# Paralel_NOR_FLASH.net
KiCad netlist of a schematic drawn in Altium Designer
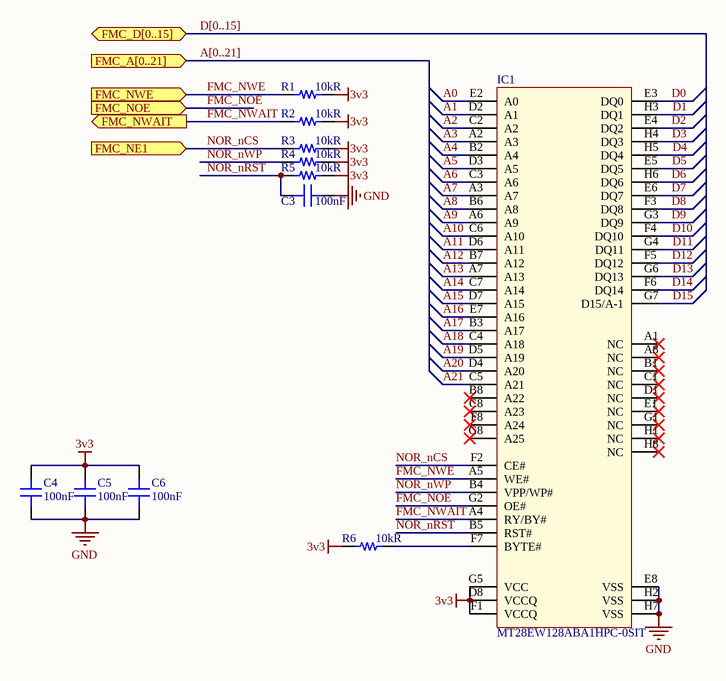
[diagram p0: Paralel NOR FLASH.SchDoc]

(export (version "E")
  (design (tool "Eeschema 10.0.6"))
  (components
    (comp (ref "C3")
      (value "100nF")
      (footprint "CAP 0603/1608")
      (description "Ceramic, SMT Capacitor")
      (fields
        (field (name "MANUFACTURER") "Samsung")
        (field (name "MANUFACTURER PART NUMBER") "CL10B104JB8NNNC")
      )
      (libsource (lib "yildizIoT Library") (part "Capacitor - Ceramic"))
    )
    (comp (ref "C4")
      (value "100nF")
      (footprint "CAP 0603/1608")
      (description "Ceramic, SMT Capacitor")
      (fields
        (field (name "MANUFACTURER") "Samsung")
        (field (name "MANUFACTURER PART NUMBER") "CL10B104JB8NNNC")
      )
      (libsource (lib "yildizIoT Library") (part "Capacitor - Ceramic"))
    )
    (comp (ref "C5")
      (value "100nF")
      (footprint "CAP 0603/1608")
      (description "Ceramic, SMT Capacitor")
      (fields
        (field (name "MANUFACTURER") "Samsung")
        (field (name "MANUFACTURER PART NUMBER") "CL10B104JB8NNNC")
      )
      (libsource (lib "yildizIoT Library") (part "Capacitor - Ceramic"))
    )
    (comp (ref "C6")
      (value "100nF")
      (footprint "CAP 0603/1608")
      (description "Ceramic, SMT Capacitor")
      (fields
        (field (name "MANUFACTURER") "Samsung")
        (field (name "MANUFACTURER PART NUMBER") "CL10B104JB8NNNC")
      )
      (libsource (lib "yildizIoT Library") (part "Capacitor - Ceramic"))
    )
    (comp (ref "IC1")
      (value "MT28EW128ABA1HPC-0SIT")
      (footprint "MICRON LBGA-64 11X13mm")
      (description "Parallel NOR Flash Embedded Memory")
      (fields (field (name "MANUFACTURER") "Micron Technology"))
      (libsource (lib "yildizIoT Library") (part "MICRON MT28EW128"))
    )
    (comp (ref "R1")
      (value "10kR")
      (footprint "RES 0603/1608")
      (description "Ceramic, SMT Capacitor")
      (fields
        (field (name "MANUFACTURER") "Stackpole Electronics")
        (field (name "MANUFACTURER PART NUMBER") "RNCP0603FTD10K0")
      )
      (libsource (lib "yildizIoT Library") (part "Resistor_Chip"))
    )
    (comp (ref "R2")
      (value "10kR")
      (footprint "RES 0603/1608")
      (description "Ceramic, SMT Capacitor")
      (fields
        (field (name "MANUFACTURER") "Stackpole Electronics")
        (field (name "MANUFACTURER PART NUMBER") "RNCP0603FTD10K0")
      )
      (libsource (lib "yildizIoT Library") (part "Resistor_Chip"))
    )
    (comp (ref "R3")
      (value "10kR")
      (footprint "RES 0603/1608")
      (description "Ceramic, SMT Capacitor")
      (fields
        (field (name "MANUFACTURER") "Stackpole Electronics")
        (field (name "MANUFACTURER PART NUMBER") "RNCP0603FTD10K0")
      )
      (libsource (lib "yildizIoT Library") (part "Resistor_Chip"))
    )
    (comp (ref "R4")
      (value "10kR")
      (footprint "RES 0603/1608")
      (description "Ceramic, SMT Capacitor")
      (fields
        (field (name "MANUFACTURER") "Stackpole Electronics")
        (field (name "MANUFACTURER PART NUMBER") "RNCP0603FTD10K0")
      )
      (libsource (lib "yildizIoT Library") (part "Resistor_Chip"))
    )
    (comp (ref "R5")
      (value "10kR")
      (footprint "RES 0603/1608")
      (description "Ceramic, SMT Capacitor")
      (fields
        (field (name "MANUFACTURER") "Stackpole Electronics")
        (field (name "MANUFACTURER PART NUMBER") "RNCP0603FTD10K0")
      )
      (libsource (lib "yildizIoT Library") (part "Resistor_Chip"))
    )
    (comp (ref "R6")
      (value "10kR")
      (footprint "RES 0603/1608")
      (description "Ceramic, SMT Capacitor")
      (fields
        (field (name "MANUFACTURER") "Stackpole Electronics")
        (field (name "MANUFACTURER PART NUMBER") "RNCP0603FTD10K0")
      )
      (libsource (lib "yildizIoT Library") (part "Resistor_Chip"))
    )
  )
  (nets
    (net (code "1") (name "/A0") (class "Default")
      (node (ref "IC1") (pin "E2") (pinfunction "A0_E2") (pintype "passive"))
    )
    (net (code "2") (name "/A1") (class "Default")
      (node (ref "IC1") (pin "D2") (pinfunction "A1_D2") (pintype "passive"))
    )
    (net (code "3") (name "/A2") (class "Default")
      (node (ref "IC1") (pin "C2") (pinfunction "A2_C2") (pintype "passive"))
    )
    (net (code "4") (name "/A3") (class "Default")
      (node (ref "IC1") (pin "A2") (pinfunction "A3_A2") (pintype "passive"))
    )
    (net (code "5") (name "/A4") (class "Default")
      (node (ref "IC1") (pin "B2") (pinfunction "A4_B2") (pintype "passive"))
    )
    (net (code "6") (name "/A5") (class "Default")
      (node (ref "IC1") (pin "D3") (pinfunction "A5_D3") (pintype "passive"))
    )
    (net (code "7") (name "/A6") (class "Default")
      (node (ref "IC1") (pin "C3") (pinfunction "A6_C3") (pintype "passive"))
    )
    (net (code "8") (name "/A7") (class "Default")
      (node (ref "IC1") (pin "A3") (pinfunction "A7_A3") (pintype "passive"))
    )
    (net (code "9") (name "/A8") (class "Default")
      (node (ref "IC1") (pin "B6") (pinfunction "A8_B6") (pintype "passive"))
    )
    (net (code "10") (name "/A9") (class "Default")
      (node (ref "IC1") (pin "A6") (pinfunction "A9_A6") (pintype "passive"))
    )
    (net (code "11") (name "/A10") (class "Default")
      (node (ref "IC1") (pin "C6") (pinfunction "A10_C6") (pintype "passive"))
    )
    (net (code "12") (name "/A11") (class "Default")
      (node (ref "IC1") (pin "D6") (pinfunction "A11_D6") (pintype "passive"))
    )
    (net (code "13") (name "/A12") (class "Default")
      (node (ref "IC1") (pin "B7") (pinfunction "A12_B7") (pintype "passive"))
    )
    (net (code "14") (name "/A13") (class "Default")
      (node (ref "IC1") (pin "A7") (pinfunction "A13_A7") (pintype "passive"))
    )
    (net (code "15") (name "/A14") (class "Default")
      (node (ref "IC1") (pin "C7") (pinfunction "A14_C7") (pintype "passive"))
    )
    (net (code "16") (name "/A15") (class "Default")
      (node (ref "IC1") (pin "D7") (pinfunction "A15_D7") (pintype "passive"))
    )
    (net (code "17") (name "/A16") (class "Default")
      (node (ref "IC1") (pin "E7") (pinfunction "A16_E7") (pintype "passive"))
    )
    (net (code "18") (name "/A17") (class "Default")
      (node (ref "IC1") (pin "B3") (pinfunction "A17_B3") (pintype "passive"))
    )
    (net (code "19") (name "/A18") (class "Default")
      (node (ref "IC1") (pin "C4") (pinfunction "A18_C4") (pintype "passive"))
    )
    (net (code "20") (name "/A19") (class "Default")
      (node (ref "IC1") (pin "D5") (pinfunction "A19_D5") (pintype "passive"))
    )
    (net (code "21") (name "/A20") (class "Default")
      (node (ref "IC1") (pin "D4") (pinfunction "A20_D4") (pintype "passive"))
    )
    (net (code "22") (name "/A21") (class "Default")
      (node (ref "IC1") (pin "C5") (pinfunction "A21_C5") (pintype "passive"))
    )
    (net (code "24") (name "/D0") (class "Default")
      (node (ref "IC1") (pin "E3") (pinfunction "DQ0_E3") (pintype "passive"))
    )
    (net (code "25") (name "/D1") (class "Default")
      (node (ref "IC1") (pin "H3") (pinfunction "DQ1_H3") (pintype "passive"))
    )
    (net (code "26") (name "/D2") (class "Default")
      (node (ref "IC1") (pin "E4") (pinfunction "DQ2_E4") (pintype "passive"))
    )
    (net (code "27") (name "/D3") (class "Default")
      (node (ref "IC1") (pin "H4") (pinfunction "DQ3_H4") (pintype "passive"))
    )
    (net (code "28") (name "/D4") (class "Default")
      (node (ref "IC1") (pin "H5") (pinfunction "DQ4_H5") (pintype "passive"))
    )
    (net (code "29") (name "/D5") (class "Default")
      (node (ref "IC1") (pin "E5") (pinfunction "DQ5_E5") (pintype "passive"))
    )
    (net (code "30") (name "/D6") (class "Default")
      (node (ref "IC1") (pin "H6") (pinfunction "DQ6_H6") (pintype "passive"))
    )
    (net (code "31") (name "/D7") (class "Default")
      (node (ref "IC1") (pin "E6") (pinfunction "DQ7_E6") (pintype "passive"))
    )
    (net (code "32") (name "/D8") (class "Default")
      (node (ref "IC1") (pin "F3") (pinfunction "DQ8_F3") (pintype "passive"))
    )
    (net (code "33") (name "/D9") (class "Default")
      (node (ref "IC1") (pin "G3") (pinfunction "DQ9_G3") (pintype "passive"))
    )
    (net (code "34") (name "/D10") (class "Default")
      (node (ref "IC1") (pin "F4") (pinfunction "DQ10_F4") (pintype "passive"))
    )
    (net (code "35") (name "/D11") (class "Default")
      (node (ref "IC1") (pin "G4") (pinfunction "DQ11_G4") (pintype "passive"))
    )
    (net (code "36") (name "/D12") (class "Default")
      (node (ref "IC1") (pin "F5") (pinfunction "DQ12_F5") (pintype "passive"))
    )
    (net (code "37") (name "/D13") (class "Default")
      (node (ref "IC1") (pin "G6") (pinfunction "DQ13_G6") (pintype "passive"))
    )
    (net (code "38") (name "/D14") (class "Default")
      (node (ref "IC1") (pin "F6") (pinfunction "DQ14_F6") (pintype "passive"))
    )
    (net (code "39") (name "/D15") (class "Default")
      (node (ref "IC1") (pin "G7") (pinfunction "D15/A-1_G7") (pintype "passive"))
    )
    (net (code "41") (name "/FMC_NOE") (class "Default")
      (node (ref "IC1") (pin "G2") (pinfunction "OE#_G2") (pintype "passive"))
    )
    (net (code "42") (name "/FMC_NWAIT") (class "Default")
      (node (ref "IC1") (pin "A4") (pinfunction "RY/BY#_A4") (pintype "passive"))
      (node (ref "R2") (pin "1") (pinfunction "1_1") (pintype "passive"))
    )
    (net (code "43") (name "/FMC_NWE") (class "Default")
      (node (ref "IC1") (pin "A5") (pinfunction "WE#_A5") (pintype "passive"))
      (node (ref "R1") (pin "1") (pinfunction "1_1") (pintype "passive"))
    )
    (net (code "44") (name "/NOR_nCS") (class "Default")
      (node (ref "IC1") (pin "F2") (pinfunction "CE#_F2") (pintype "passive"))
      (node (ref "R3") (pin "1") (pinfunction "1_1") (pintype "passive"))
    )
    (net (code "45") (name "/NOR_nRST") (class "Default")
      (node (ref "C3") (pin "1") (pinfunction "1_1") (pintype "passive"))
      (node (ref "IC1") (pin "B5") (pinfunction "RST#_B5") (pintype "passive"))
      (node (ref "R5") (pin "1") (pinfunction "1_1") (pintype "passive"))
    )
    (net (code "46") (name "/NOR_nWP") (class "Default")
      (node (ref "IC1") (pin "B4") (pinfunction "VPP/WP#_B4") (pintype "passive"))
      (node (ref "R4") (pin "1") (pinfunction "1_1") (pintype "passive"))
    )
    (net (code "47") (name "3v3") (class "Default")
      (node (ref "C4") (pin "1") (pinfunction "1_1") (pintype "passive"))
      (node (ref "C5") (pin "1") (pinfunction "1_1") (pintype "passive"))
      (node (ref "C6") (pin "1") (pinfunction "1_1") (pintype "passive"))
      (node (ref "IC1") (pin "D8") (pinfunction "VCCQ_D8") (pintype "passive"))
      (node (ref "IC1") (pin "F1") (pinfunction "VCCQ_F1") (pintype "passive"))
      (node (ref "IC1") (pin "G5") (pinfunction "VCC_G5") (pintype "passive"))
      (node (ref "R1") (pin "2") (pinfunction "2_2") (pintype "passive"))
      (node (ref "R2") (pin "2") (pinfunction "2_2") (pintype "passive"))
      (node (ref "R3") (pin "2") (pinfunction "2_2") (pintype "passive"))
      (node (ref "R4") (pin "2") (pinfunction "2_2") (pintype "passive"))
      (node (ref "R5") (pin "2") (pinfunction "2_2") (pintype "passive"))
      (node (ref "R6") (pin "1") (pinfunction "1_1") (pintype "passive"))
    )
    (net (code "48") (name "GND") (class "Default")
      (node (ref "C3") (pin "2") (pinfunction "2_2") (pintype "passive"))
      (node (ref "C4") (pin "2") (pinfunction "2_2") (pintype "passive"))
      (node (ref "C5") (pin "2") (pinfunction "2_2") (pintype "passive"))
      (node (ref "C6") (pin "2") (pinfunction "2_2") (pintype "passive"))
      (node (ref "IC1") (pin "E8") (pinfunction "VSS_E8") (pintype "passive"))
      (node (ref "IC1") (pin "H2") (pinfunction "VSS_H2") (pintype "passive"))
      (node (ref "IC1") (pin "H7") (pinfunction "VSS_H7") (pintype "passive"))
    )
    (net (code "49") (name "Net-(IC1-BYTE#)") (class "Default")
      (node (ref "IC1") (pin "F7") (pinfunction "BYTE#_F7") (pintype "passive"))
      (node (ref "R6") (pin "2") (pinfunction "2_2") (pintype "passive"))
    )
    (net (code "50") (name "unconnected-(IC1-A22-PadB8)") (class "Default")
      (node (ref "IC1") (pin "B8") (pinfunction "A22_B8") (pintype "passive+no_connect"))
    )
    (net (code "51") (name "unconnected-(IC1-A23-PadC8)") (class "Default")
      (node (ref "IC1") (pin "C8") (pinfunction "A23_C8") (pintype "passive+no_connect"))
    )
    (net (code "52") (name "unconnected-(IC1-A24-PadF8)") (class "Default")
      (node (ref "IC1") (pin "F8") (pinfunction "A24_F8") (pintype "passive+no_connect"))
    )
    (net (code "53") (name "unconnected-(IC1-A25-PadG8)") (class "Default")
      (node (ref "IC1") (pin "G8") (pinfunction "A25_G8") (pintype "passive+no_connect"))
    )
    (net (code "54") (name "unconnected-(IC1-NC-PadA1)") (class "Default")
      (node (ref "IC1") (pin "A1") (pinfunction "NC_A1") (pintype "passive+no_connect"))
    )
    (net (code "55") (name "unconnected-(IC1-NC-PadA8)") (class "Default")
      (node (ref "IC1") (pin "A8") (pinfunction "NC_A8") (pintype "passive+no_connect"))
    )
    (net (code "56") (name "unconnected-(IC1-NC-PadB1)") (class "Default")
      (node (ref "IC1") (pin "B1") (pinfunction "NC_B1") (pintype "passive+no_connect"))
    )
    (net (code "57") (name "unconnected-(IC1-NC-PadC1)") (class "Default")
      (node (ref "IC1") (pin "C1") (pinfunction "NC_C1") (pintype "passive+no_connect"))
    )
    (net (code "58") (name "unconnected-(IC1-NC-PadD1)") (class "Default")
      (node (ref "IC1") (pin "D1") (pinfunction "NC_D1") (pintype "passive+no_connect"))
    )
    (net (code "59") (name "unconnected-(IC1-NC-PadE1)") (class "Default")
      (node (ref "IC1") (pin "E1") (pinfunction "NC_E1") (pintype "passive+no_connect"))
    )
    (net (code "60") (name "unconnected-(IC1-NC-PadG1)") (class "Default")
      (node (ref "IC1") (pin "G1") (pinfunction "NC_G1") (pintype "passive+no_connect"))
    )
    (net (code "61") (name "unconnected-(IC1-NC-PadH1)") (class "Default")
      (node (ref "IC1") (pin "H1") (pinfunction "NC_H1") (pintype "passive+no_connect"))
    )
    (net (code "62") (name "unconnected-(IC1-NC-PadH8)") (class "Default")
      (node (ref "IC1") (pin "H8") (pinfunction "NC_H8") (pintype "passive+no_connect"))
    )
  )
)
